# trip-10ma-rccb-only-tool.net
KiCad netlist of a schematic drawn in EAGLE
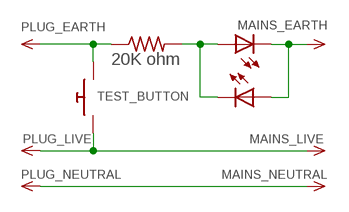
[diagram p0: schematic, sheet 1]

(export (version "E")
  (design (tool "Eeschema 10.0.6"))
  (components
    (comp (ref "LED1")
      (value "LED5MM")
      (footprint "eagle-import:LED5MM")
      (libsource (lib "eagle-import") (part "LED5MM"))
    )
    (comp (ref "LED2")
      (value "LED5MM")
      (footprint "eagle-import:LED5MM")
      (libsource (lib "eagle-import") (part "LED5MM"))
    )
    (comp (ref "R1")
      (value "20K ohm")
      (footprint "eagle-import:0207_10")
      (libsource (lib "eagle-import") (part "R-US_0207/10"))
    )
    (comp (ref "TEST_BUTTON")
      (value "SWITCH_PUSHBUTTONC&K_KSS")
      (footprint "eagle-import:BTN_CK_KSS")
      (libsource (lib "eagle-import") (part "SWITCH_PUSHBUTTONC&K_KSS"))
    )
  )
  (nets
    (net (code "1") (name "Net-(LED2-C)") (class "Default")
      (node (ref "LED1") (pin "A") (pinfunction "A_A") (pintype "passive"))
      (node (ref "LED2") (pin "K") (pinfunction "C_K") (pintype "passive"))
      (node (ref "R1") (pin "2") (pinfunction "2_2") (pintype "passive"))
    )
    (net (code "2") (name "SUPPLY") (class "Default")
      (node (ref "LED1") (pin "K") (pinfunction "C_K") (pintype "passive"))
      (node (ref "LED2") (pin "A") (pinfunction "A_A") (pintype "passive"))
      (node (ref "R1") (pin "1") (pinfunction "1_1") (pintype "passive"))
      (node (ref "TEST_BUTTON") (pin "P$1") (pinfunction "P$1_P$1") (pintype "passive"))
      (node (ref "TEST_BUTTON") (pin "P$2") (pinfunction "P$2_P$2") (pintype "passive"))
    )
  )
)
